# Placa_V1.net
KiCad netlist of a schematic drawn in EAGLE
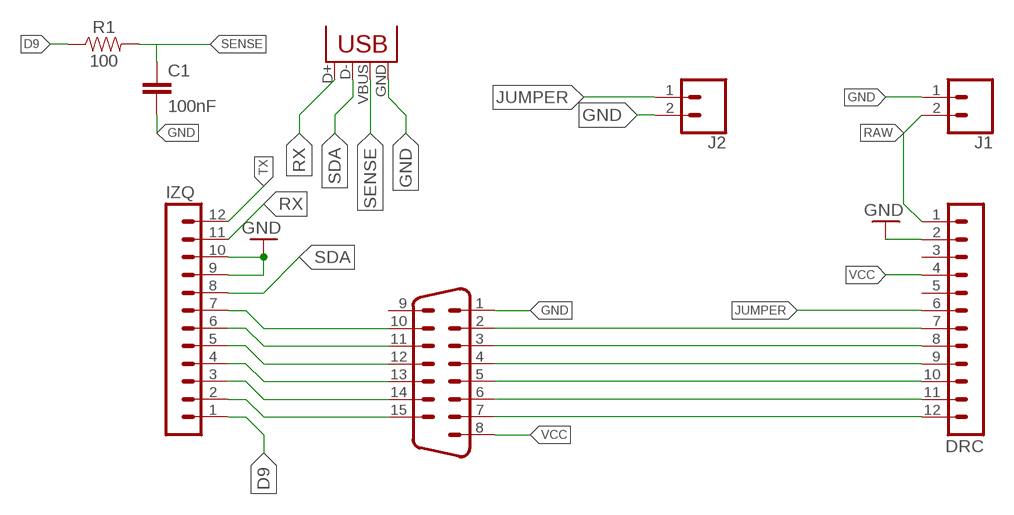
[diagram p0: schematic, sheet 1]

(export (version "E")
  (design (tool "Eeschema 10.0.6"))
  (components
    (comp (ref "C1")
      (value "100nF")
      (footprint "eagle-import:0603")
      (libsource (lib "eagle-import") (part "0.1UF-0603-25V-5%"))
    )
    (comp (ref "DRC")
      (value "MA12-1")
      (footprint "eagle-import:MA12-1")
      (libsource (lib "eagle-import") (part "MA12-1"))
    )
    (comp (ref "IZQ")
      (value "MA12-1")
      (footprint "eagle-import:MA12-1")
      (libsource (lib "eagle-import") (part "MA12-1"))
    )
    (comp (ref "J1")
      (value "CONN_02")
      (footprint "eagle-import:1X02")
      (libsource (lib "eagle-import") (part "CONN_02"))
    )
    (comp (ref "J2")
      (value "CONN_02")
      (footprint "eagle-import:1X02")
      (libsource (lib "eagle-import") (part "CONN_02"))
    )
    (comp (ref "R1")
      (value "100")
      (footprint "eagle-import:0603")
      (libsource (lib "eagle-import") (part "100OHM-0603-1/4W-5%"))
    )
    (comp (ref "X2")
      (value "USB-B-H")
      (footprint "eagle-import:USB-B-H")
      (libsource (lib "eagle-import") (part "USB-B-H"))
    )
    (comp (ref "X3")
      (value "M15V")
      (footprint "eagle-import:M15V")
      (libsource (lib "eagle-import") (part "M15V"))
    )
  )
  (nets
    (net (code "1") (name "D9") (class "Default")
      (node (ref "IZQ") (pin "1") (pinfunction "1_1") (pintype "passive"))
      (node (ref "R1") (pin "1") (pinfunction "1_1") (pintype "passive"))
    )
    (net (code "2") (name "GND") (class "Default")
      (node (ref "C1") (pin "2") (pinfunction "2_2") (pintype "passive"))
      (node (ref "DRC") (pin "2") (pinfunction "2_2") (pintype "passive"))
      (node (ref "IZQ") (pin "10") (pinfunction "10_10") (pintype "passive"))
      (node (ref "IZQ") (pin "9") (pinfunction "9_9") (pintype "passive"))
      (node (ref "J1") (pin "1") (pinfunction "1_1") (pintype "passive"))
      (node (ref "J2") (pin "2") (pinfunction "2_2") (pintype "passive"))
      (node (ref "X2") (pin "GND") (pinfunction "GND_GND") (pintype "bidirectional"))
      (node (ref "X3") (pin "1") (pinfunction "1_1") (pintype "passive"))
    )
    (net (code "3") (name "JUMPER") (class "Default")
      (node (ref "DRC") (pin "6") (pinfunction "6_6") (pintype "passive"))
      (node (ref "J2") (pin "1") (pinfunction "1_1") (pintype "passive"))
    )
    (net (code "4") (name "Net-(DRC-Pad7)") (class "Default")
      (node (ref "DRC") (pin "7") (pinfunction "7_7") (pintype "passive"))
      (node (ref "X3") (pin "2") (pinfunction "2_2") (pintype "passive"))
    )
    (net (code "5") (name "Net-(DRC-Pad8)") (class "Default")
      (node (ref "DRC") (pin "8") (pinfunction "8_8") (pintype "passive"))
      (node (ref "X3") (pin "3") (pinfunction "3_3") (pintype "passive"))
    )
    (net (code "6") (name "Net-(DRC-Pad9)") (class "Default")
      (node (ref "DRC") (pin "9") (pinfunction "9_9") (pintype "passive"))
      (node (ref "X3") (pin "4") (pinfunction "4_4") (pintype "passive"))
    )
    (net (code "7") (name "Net-(DRC-Pad10)") (class "Default")
      (node (ref "DRC") (pin "10") (pinfunction "10_10") (pintype "passive"))
      (node (ref "X3") (pin "5") (pinfunction "5_5") (pintype "passive"))
    )
    (net (code "8") (name "Net-(DRC-Pad11)") (class "Default")
      (node (ref "DRC") (pin "11") (pinfunction "11_11") (pintype "passive"))
      (node (ref "X3") (pin "6") (pinfunction "6_6") (pintype "passive"))
    )
    (net (code "9") (name "Net-(DRC-Pad12)") (class "Default")
      (node (ref "DRC") (pin "12") (pinfunction "12_12") (pintype "passive"))
      (node (ref "X3") (pin "7") (pinfunction "7_7") (pintype "passive"))
    )
    (net (code "10") (name "Net-(IZQ-Pad2)") (class "Default")
      (node (ref "IZQ") (pin "2") (pinfunction "2_2") (pintype "passive"))
      (node (ref "X3") (pin "15") (pinfunction "15_15") (pintype "passive"))
    )
    (net (code "11") (name "Net-(IZQ-Pad3)") (class "Default")
      (node (ref "IZQ") (pin "3") (pinfunction "3_3") (pintype "passive"))
      (node (ref "X3") (pin "14") (pinfunction "14_14") (pintype "passive"))
    )
    (net (code "12") (name "Net-(IZQ-Pad4)") (class "Default")
      (node (ref "IZQ") (pin "4") (pinfunction "4_4") (pintype "passive"))
      (node (ref "X3") (pin "13") (pinfunction "13_13") (pintype "passive"))
    )
    (net (code "13") (name "Net-(IZQ-Pad5)") (class "Default")
      (node (ref "IZQ") (pin "5") (pinfunction "5_5") (pintype "passive"))
      (node (ref "X3") (pin "12") (pinfunction "12_12") (pintype "passive"))
    )
    (net (code "14") (name "Net-(IZQ-Pad6)") (class "Default")
      (node (ref "IZQ") (pin "6") (pinfunction "6_6") (pintype "passive"))
      (node (ref "X3") (pin "11") (pinfunction "11_11") (pintype "passive"))
    )
    (net (code "15") (name "Net-(IZQ-Pad7)") (class "Default")
      (node (ref "IZQ") (pin "7") (pinfunction "7_7") (pintype "passive"))
      (node (ref "X3") (pin "10") (pinfunction "10_10") (pintype "passive"))
    )
    (net (code "16") (name "RAW") (class "Default")
      (node (ref "DRC") (pin "1") (pinfunction "1_1") (pintype "passive"))
      (node (ref "J1") (pin "2") (pinfunction "2_2") (pintype "passive"))
    )
    (net (code "17") (name "RX") (class "Default")
      (node (ref "IZQ") (pin "11") (pinfunction "11_11") (pintype "passive"))
      (node (ref "X2") (pin "D+") (pinfunction "D+_D+") (pintype "bidirectional"))
    )
    (net (code "18") (name "SDA") (class "Default")
      (node (ref "IZQ") (pin "8") (pinfunction "8_8") (pintype "passive"))
      (node (ref "X2") (pin "D-") (pinfunction "D-_D-") (pintype "bidirectional"))
    )
    (net (code "19") (name "SENSE") (class "Default")
      (node (ref "C1") (pin "1") (pinfunction "1_1") (pintype "passive"))
      (node (ref "R1") (pin "2") (pinfunction "2_2") (pintype "passive"))
      (node (ref "X2") (pin "VBUS") (pinfunction "VBUS_VBUS") (pintype "bidirectional"))
    )
    (net (code "20") (name "TX") (class "Default")
      (node (ref "IZQ") (pin "12") (pinfunction "12_12") (pintype "passive"))
    )
    (net (code "21") (name "VCC") (class "Default")
      (node (ref "DRC") (pin "4") (pinfunction "4_4") (pintype "passive"))
      (node (ref "X3") (pin "8") (pinfunction "8_8") (pintype "passive"))
    )
    (net (code "22") (name "unconnected-(DRC-Pad3)") (class "Default")
      (node (ref "DRC") (pin "3") (pinfunction "3_3") (pintype "passive"))
    )
    (net (code "23") (name "unconnected-(DRC-Pad5)") (class "Default")
      (node (ref "DRC") (pin "5") (pinfunction "5_5") (pintype "passive"))
    )
    (net (code "24") (name "unconnected-(X3-Pad9)") (class "Default")
      (node (ref "X3") (pin "9") (pinfunction "9_9") (pintype "passive"))
    )
  )
)
